# power.net
KiCad netlist of a schematic drawn in Altium Designer
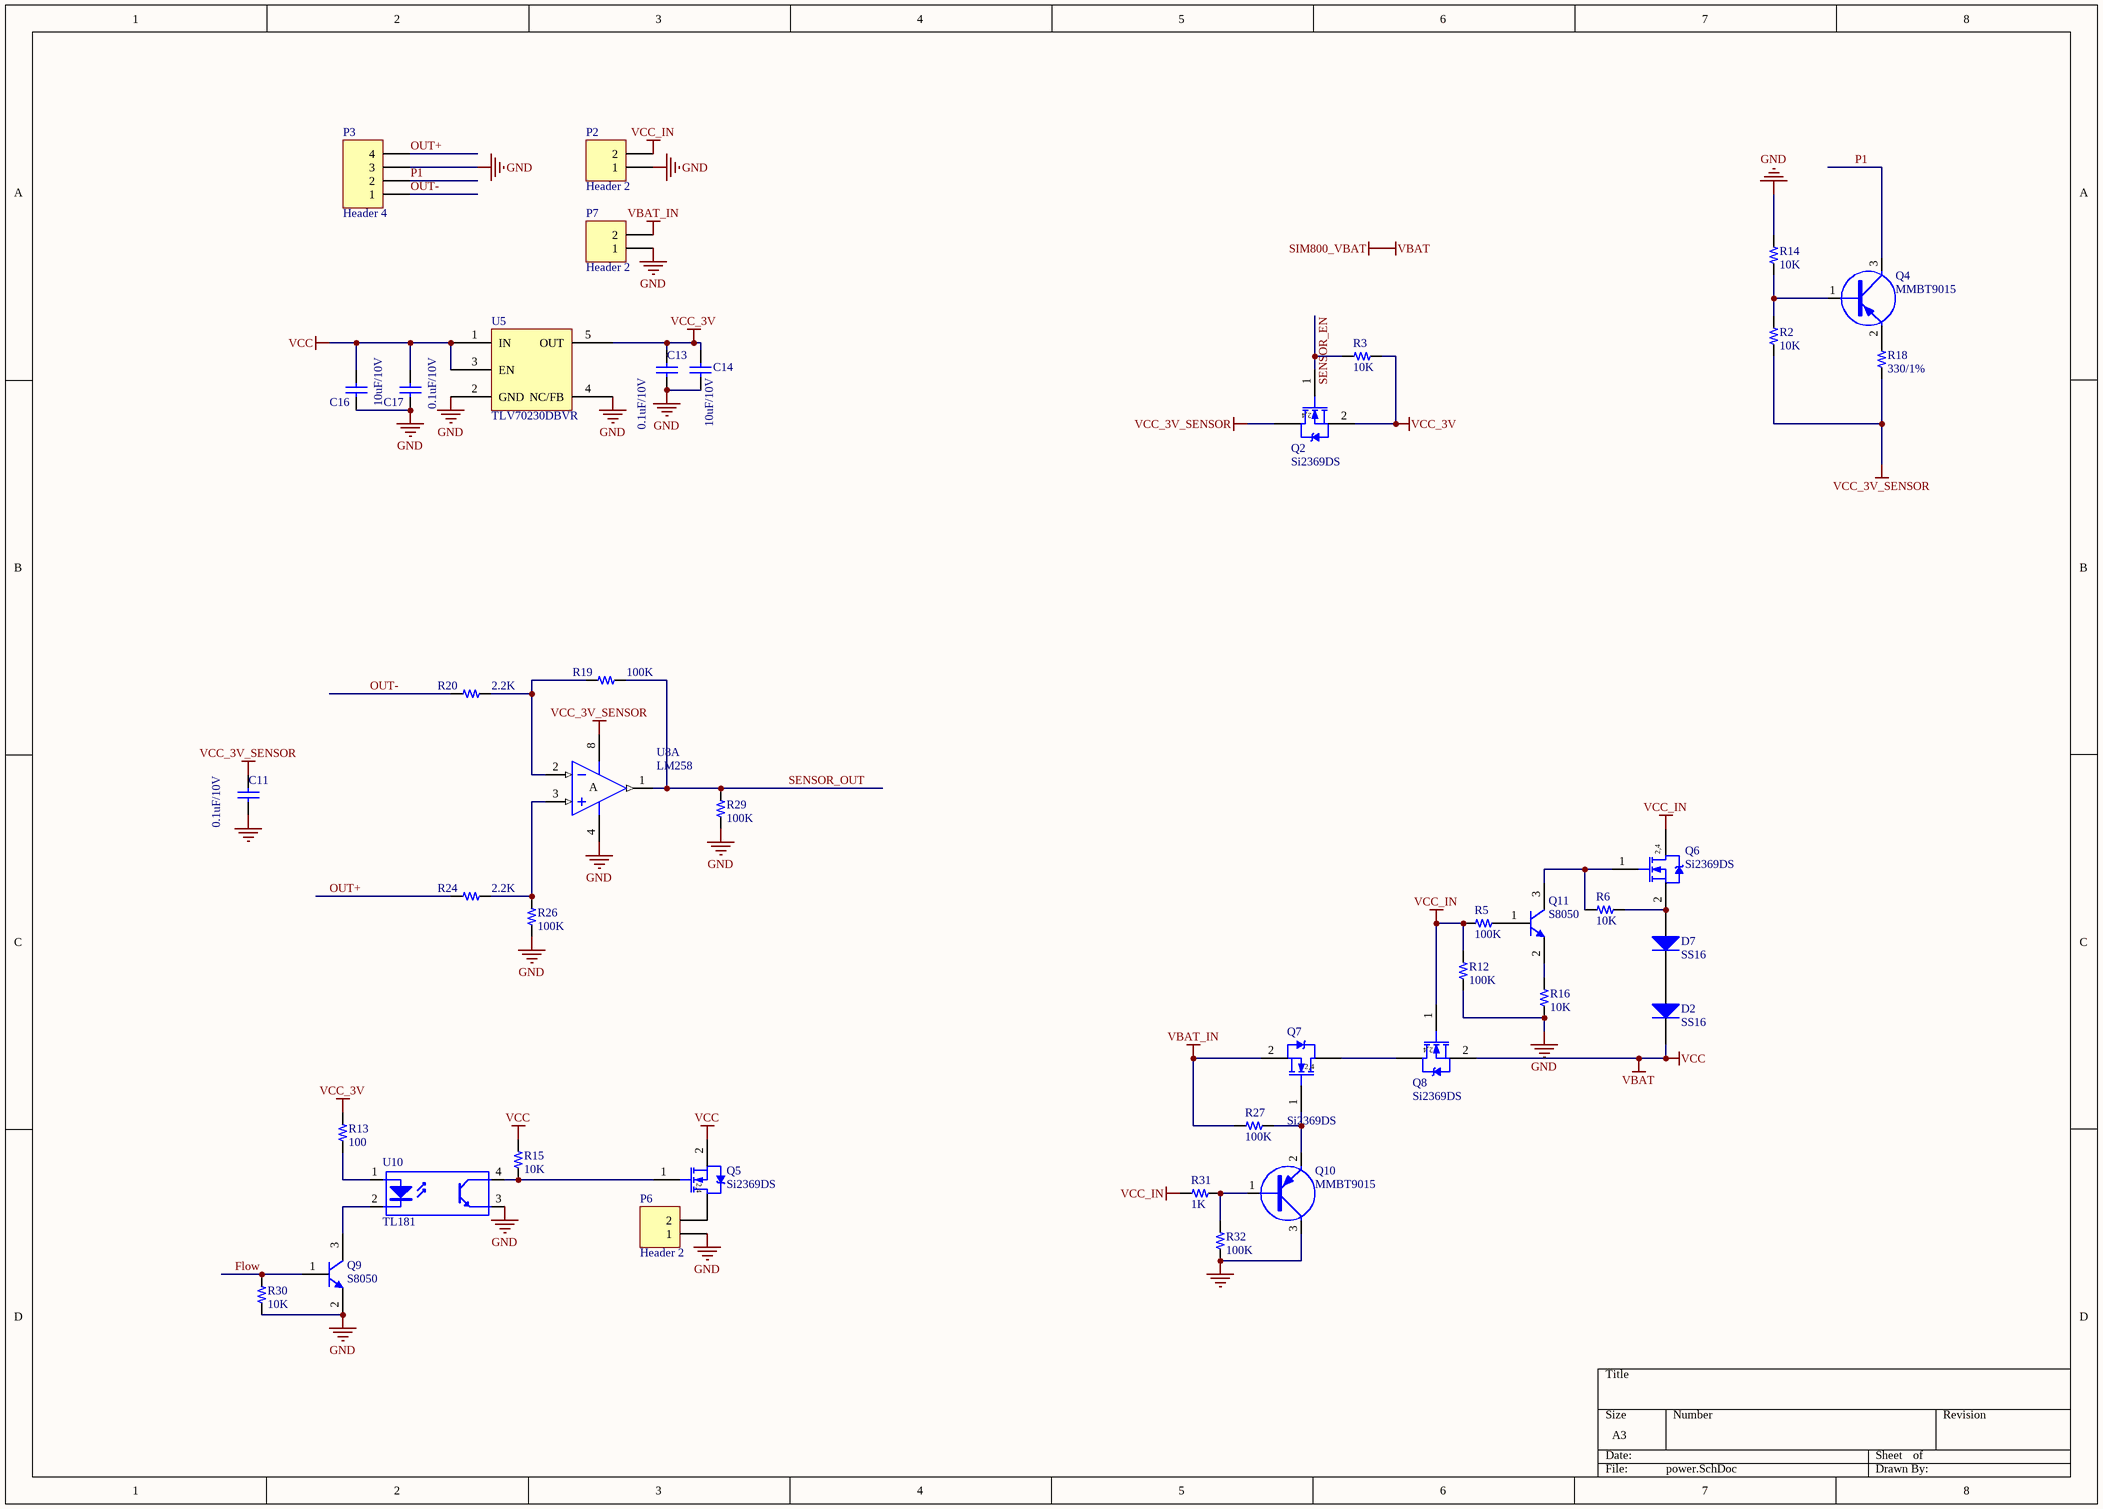
[diagram p0: power.SchDoc]

(export (version "E")
  (design (tool "Eeschema 10.0.6"))
  (components
    (comp (ref "C11")
      (value "0.1uF/10V")
      (footprint "0603C")
      (description "Capacitor")
      (fields (field (name "PUBLISHER") "Altium Limited"))
      (libsource (lib "Miscellaneous Devices") (part "Cap"))
    )
    (comp (ref "C13")
      (value "0.1uF/10V")
      (footprint "0603C")
      (description "Capacitor")
      (fields (field (name "PUBLISHER") "Altium Limited"))
      (libsource (lib "Miscellaneous Devices") (part "Cap"))
    )
    (comp (ref "C14")
      (value "10uF/10V")
      (footprint "0603C")
      (description "Capacitor")
      (fields (field (name "PUBLISHER") "Altium Limited"))
      (libsource (lib "Miscellaneous Devices") (part "Cap"))
    )
    (comp (ref "C16")
      (value "10uF/10V")
      (footprint "0603C")
      (description "Capacitor")
      (fields (field (name "PUBLISHER") "Altium Limited"))
      (libsource (lib "Miscellaneous Devices") (part "Cap"))
    )
    (comp (ref "C17")
      (value "0.1uF/10V")
      (footprint "0603C")
      (description "Capacitor")
      (fields (field (name "PUBLISHER") "Altium Limited"))
      (libsource (lib "Miscellaneous Devices") (part "Cap"))
    )
    (comp (ref "D2")
      (value "SS16")
      (footprint "SMA")
      (description "High Conductance Fast Diode")
      (fields (field (name "PUBLISHER") "Altium Limited"))
      (libsource (lib "Miscellaneous Devices") (part "Diode 1N4148"))
    )
    (comp (ref "D7")
      (value "SS16")
      (footprint "SMA")
      (description "High Conductance Fast Diode")
      (fields (field (name "PUBLISHER") "Altium Limited"))
      (libsource (lib "Miscellaneous Devices") (part "Diode 1N4148"))
    )
    (comp (ref "P2")
      (value "Header 2")
      (footprint "2X2.54MM")
      (description "Header, 2-Pin")
      (fields (field (name "PUBLISHER") "Altium Limited"))
      (libsource (lib "Miscellaneous Connectors") (part "Header 2"))
    )
    (comp (ref "P3")
      (value "Header 4")
      (footprint "HDR1X4")
      (description "Header, 4-Pin")
      (fields (field (name "PUBLISHER") "Altium Limited"))
      (libsource (lib "Miscellaneous Connectors") (part "Header 4"))
    )
    (comp (ref "P6")
      (value "Header 2")
      (footprint "HDR1X2")
      (description "Header, 2-Pin")
      (fields (field (name "PUBLISHER") "Altium Limited"))
      (libsource (lib "Miscellaneous Connectors") (part "Header 2"))
    )
    (comp (ref "P7")
      (value "Header 2")
      (footprint "2X2.54MM")
      (description "Header, 2-Pin")
      (fields (field (name "PUBLISHER") "Altium Limited"))
      (libsource (lib "Miscellaneous Connectors") (part "Header 2"))
    )
    (comp (ref "Q2")
      (value "Si2369DS")
      (footprint "SOT23-3")
      (description "BUK92150-55A")
      (fields (field (name "PUBLISHER") "Altium Limited"))
      (libsource (lib "Schlib1") (part "BUK92150-55A"))
    )
    (comp (ref "Q4") (value "MMBT9015") (footprint "SOT23-3") (libsource (lib "Schlib1") (part "PNP")))
    (comp (ref "Q5")
      (value "Si2369DS")
      (footprint "SOT23-3")
      (description "BUK92150-55A")
      (fields (field (name "PUBLISHER") "Altium Limited"))
      (libsource (lib "") (part "BUK92150-55A_1"))
    )
    (comp (ref "Q6")
      (value "Si2369DS")
      (footprint "SOT23-3")
      (description "BUK92150-55A")
      (fields (field (name "PUBLISHER") "Altium Limited"))
      (libsource (lib "") (part "BUK92150-55A_1"))
    )
    (comp (ref "Q7")
      (value "Si2369DS")
      (footprint "SOT23-3")
      (description "BUK92150-55A")
      (fields (field (name "PUBLISHER") "Altium Limited"))
      (libsource (lib "Schlib1") (part "BUK92150-55A"))
    )
    (comp (ref "Q8")
      (value "Si2369DS")
      (footprint "SOT23-3")
      (description "BUK92150-55A")
      (fields (field (name "PUBLISHER") "Altium Limited"))
      (libsource (lib "Schlib1") (part "BUK92150-55A"))
    )
    (comp (ref "Q9") (value "S8050") (footprint "SOT23-3") (libsource (lib "Schlib1") (part "NPN")))
    (comp (ref "Q10") (value "MMBT9015") (footprint "SOT23-3") (libsource (lib "Schlib1") (part "PNP")))
    (comp (ref "Q11") (value "S8050") (footprint "SOT23-3") (libsource (lib "Schlib1") (part "NPN")))
    (comp (ref "R2") (value "10K") (footprint "0603R") (description "R") (libsource (lib "JRJ_1") (part "R")))
    (comp (ref "R3") (value "10K") (footprint "0603R") (description "R") (libsource (lib "JRJ_1") (part "R")))
    (comp (ref "R5")
      (value "100K")
      (footprint "0603R")
      (description "R")
      (libsource (lib "JRJ_1") (part "R"))
    )
    (comp (ref "R6") (value "10K") (footprint "0603R") (description "R") (libsource (lib "JRJ_1") (part "R")))
    (comp (ref "R12")
      (value "100K")
      (footprint "0603R")
      (description "R")
      (libsource (lib "JRJ_1") (part "R"))
    )
    (comp (ref "R13")
      (value "100")
      (footprint "0603R")
      (description "R")
      (libsource (lib "JRJ_1") (part "R"))
    )
    (comp (ref "R14")
      (value "10K")
      (footprint "0603R")
      (description "R")
      (libsource (lib "JRJ_1") (part "R"))
    )
    (comp (ref "R15")
      (value "10K")
      (footprint "0603R")
      (description "R")
      (libsource (lib "JRJ_1") (part "R"))
    )
    (comp (ref "R16")
      (value "10K")
      (footprint "0603R")
      (description "R")
      (libsource (lib "JRJ_1") (part "R"))
    )
    (comp (ref "R18")
      (value "330/1%")
      (footprint "0603R")
      (description "R")
      (libsource (lib "JRJ_1") (part "R"))
    )
    (comp (ref "R19")
      (value "100K")
      (footprint "0603R")
      (description "R")
      (libsource (lib "JRJ_1") (part "R"))
    )
    (comp (ref "R20")
      (value "2.2K")
      (footprint "0603R")
      (description "R")
      (libsource (lib "JRJ_1") (part "R"))
    )
    (comp (ref "R24")
      (value "2.2K")
      (footprint "0603R")
      (description "R")
      (libsource (lib "JRJ_1") (part "R"))
    )
    (comp (ref "R26")
      (value "100K")
      (footprint "0603R")
      (description "R")
      (libsource (lib "JRJ_1") (part "R"))
    )
    (comp (ref "R27")
      (value "100K")
      (footprint "0603R")
      (description "R")
      (libsource (lib "JRJ_1") (part "R"))
    )
    (comp (ref "R29")
      (value "100K")
      (footprint "0603R")
      (description "R")
      (libsource (lib "JRJ_1") (part "R"))
    )
    (comp (ref "R30")
      (value "10K")
      (footprint "0603R")
      (description "R")
      (libsource (lib "JRJ_1") (part "R"))
    )
    (comp (ref "R31") (value "1K") (footprint "0603R") (description "R") (libsource (lib "JRJ_1") (part "R")))
    (comp (ref "R32")
      (value "100K")
      (footprint "0603R")
      (description "R")
      (libsource (lib "JRJ_1") (part "R"))
    )
    (comp (ref "U5")
      (value "TLV70230DBVR")
      (footprint "SOT23-5(DBV)")
      (libsource (lib "Schlib_20110825") (part "TLV70230DBVR"))
    )
    (comp (ref "U8") (value "LM258") (footprint "so-8") (libsource (lib "Schlib_20110825") (part "LM258")))
    (comp (ref "U10")
      (value "TL181")
      (footprint "DIP-4")
      (description "4-Pin Phototransistor Optocoupler")
      (fields (field (name "PUBLISHER") "Altium Limited"))
      (libsource (lib "Miscellaneous Devices") (part "Optoisolator1"))
    )
  )
  (nets
    (net (code "1") (name "/Flow") (class "Default")
      (node (ref "Q9") (pin "1") (pinfunction "B_1") (pintype "passive"))
      (node (ref "R30") (pin "2") (pintype "passive"))
    )
    (net (code "2") (name "/OUT+") (class "Default")
      (node (ref "P3") (pin "4") (pinfunction "4_4") (pintype "passive"))
      (node (ref "R24") (pin "1") (pintype "passive"))
    )
    (net (code "3") (name "/OUT-") (class "Default")
      (node (ref "P3") (pin "1") (pinfunction "1_1") (pintype "passive"))
      (node (ref "R20") (pin "1") (pintype "passive"))
    )
    (net (code "4") (name "/P1") (class "Default")
      (node (ref "P3") (pin "2") (pinfunction "2_2") (pintype "passive"))
      (node (ref "Q4") (pin "3") (pinfunction "C_3") (pintype "passive"))
    )
    (net (code "5") (name "/SENSOR_EN") (class "Default")
      (node (ref "Q2") (pin "1") (pinfunction "G_1") (pintype "passive"))
      (node (ref "R3") (pin "2") (pintype "passive"))
    )
    (net (code "6") (name "/SENSOR_OUT") (class "Default")
      (node (ref "R19") (pin "2") (pintype "passive"))
      (node (ref "R29") (pin "2") (pintype "passive"))
      (node (ref "U8") (pin "1") (pinfunction "OUT_1") (pintype "output"))
    )
    (net (code "7") (name "GND") (class "Default")
      (node (ref "C11") (pin "2") (pinfunction "2_2") (pintype "passive"))
      (node (ref "C13") (pin "2") (pinfunction "2_2") (pintype "passive"))
      (node (ref "C14") (pin "1") (pinfunction "1_1") (pintype "passive"))
      (node (ref "C16") (pin "1") (pinfunction "1_1") (pintype "passive"))
      (node (ref "C17") (pin "2") (pinfunction "2_2") (pintype "passive"))
      (node (ref "P2") (pin "1") (pinfunction "1_1") (pintype "passive"))
      (node (ref "P3") (pin "3") (pinfunction "3_3") (pintype "passive"))
      (node (ref "P6") (pin "1") (pinfunction "1_1") (pintype "passive"))
      (node (ref "P7") (pin "1") (pinfunction "1_1") (pintype "passive"))
      (node (ref "Q10") (pin "3") (pinfunction "C_3") (pintype "passive"))
      (node (ref "Q9") (pin "2") (pinfunction "E_2") (pintype "passive"))
      (node (ref "R12") (pin "2") (pintype "passive"))
      (node (ref "R14") (pin "2") (pintype "passive"))
      (node (ref "R16") (pin "1") (pintype "passive"))
      (node (ref "R26") (pin "1") (pintype "passive"))
      (node (ref "R29") (pin "1") (pintype "passive"))
      (node (ref "R30") (pin "1") (pintype "passive"))
      (node (ref "R32") (pin "1") (pintype "passive"))
      (node (ref "U10") (pin "3") (pinfunction "E_3") (pintype "passive"))
      (node (ref "U5") (pin "2") (pinfunction "GND_2") (pintype "passive"))
      (node (ref "U5") (pin "4") (pinfunction "NC/FB_4") (pintype "passive"))
      (node (ref "U8") (pin "4") (pinfunction "V-_4") (pintype "power_in"))
    )
    (net (code "8") (name "Net-(D2-A)") (class "Default")
      (node (ref "D2") (pin "1") (pinfunction "A_1") (pintype "passive"))
      (node (ref "D7") (pin "2") (pinfunction "K_2") (pintype "passive"))
    )
    (net (code "9") (name "Net-(D7-A)") (class "Default")
      (node (ref "D7") (pin "1") (pinfunction "A_1") (pintype "passive"))
      (node (ref "Q6") (pin "2") (pinfunction "S_2") (pintype "passive"))
      (node (ref "R6") (pin "1") (pintype "passive"))
    )
    (net (code "10") (name "Net-(Q4-B)") (class "Default")
      (node (ref "Q4") (pin "1") (pinfunction "B_1") (pintype "passive"))
      (node (ref "R14") (pin "1") (pintype "passive"))
      (node (ref "R2") (pin "2") (pintype "passive"))
    )
    (net (code "11") (name "Net-(Q4-E)") (class "Default")
      (node (ref "Q4") (pin "2") (pinfunction "E_2") (pintype "passive"))
      (node (ref "R18") (pin "2") (pintype "passive"))
    )
    (net (code "12") (name "Net-(Q5-D)") (class "Default")
      (node (ref "P6") (pin "2") (pinfunction "2_2") (pintype "passive"))
      (node (ref "Q5") (pin "3") (pinfunction "D_3") (pintype "passive"))
    )
    (net (code "13") (name "Net-(Q5-G)") (class "Default")
      (node (ref "Q5") (pin "1") (pinfunction "G_1") (pintype "passive"))
      (node (ref "R15") (pin "1") (pintype "passive"))
      (node (ref "U10") (pin "4") (pinfunction "C_4") (pintype "passive"))
    )
    (net (code "14") (name "Net-(Q7-D)") (class "Default")
      (node (ref "Q7") (pin "3") (pinfunction "D_3") (pintype "passive"))
      (node (ref "Q8") (pin "3") (pinfunction "D_3") (pintype "passive"))
    )
    (net (code "15") (name "Net-(Q9-C)") (class "Default")
      (node (ref "Q9") (pin "3") (pinfunction "C_3") (pintype "passive"))
      (node (ref "U10") (pin "2") (pinfunction "K_2") (pintype "passive"))
    )
    (net (code "16") (name "Net-(Q10-B)") (class "Default")
      (node (ref "Q10") (pin "1") (pinfunction "B_1") (pintype "passive"))
      (node (ref "R31") (pin "2") (pintype "passive"))
      (node (ref "R32") (pin "2") (pintype "passive"))
    )
    (net (code "17") (name "Net-(Q10-E)") (class "Default")
      (node (ref "Q10") (pin "2") (pinfunction "E_2") (pintype "passive"))
      (node (ref "Q7") (pin "1") (pinfunction "G_1") (pintype "passive"))
      (node (ref "R27") (pin "2") (pintype "passive"))
    )
    (net (code "18") (name "Net-(Q11-B)") (class "Default")
      (node (ref "Q11") (pin "1") (pinfunction "B_1") (pintype "passive"))
      (node (ref "R5") (pin "2") (pintype "passive"))
    )
    (net (code "19") (name "Net-(Q11-C)") (class "Default")
      (node (ref "Q11") (pin "3") (pinfunction "C_3") (pintype "passive"))
      (node (ref "Q6") (pin "1") (pinfunction "G_1") (pintype "passive"))
      (node (ref "R6") (pin "2") (pintype "passive"))
    )
    (net (code "20") (name "Net-(Q11-E)") (class "Default")
      (node (ref "Q11") (pin "2") (pinfunction "E_2") (pintype "passive"))
      (node (ref "R16") (pin "2") (pintype "passive"))
    )
    (net (code "21") (name "Net-(U8A-IN+)") (class "Default")
      (node (ref "R24") (pin "2") (pintype "passive"))
      (node (ref "R26") (pin "2") (pintype "passive"))
      (node (ref "U8") (pin "3") (pinfunction "IN+_3") (pintype "input"))
    )
    (net (code "22") (name "Net-(U8A-IN-)") (class "Default")
      (node (ref "R19") (pin "1") (pintype "passive"))
      (node (ref "R20") (pin "2") (pintype "passive"))
      (node (ref "U8") (pin "2") (pinfunction "IN-_2") (pintype "input"))
    )
    (net (code "23") (name "Net-(U10-A)") (class "Default")
      (node (ref "R13") (pin "1") (pintype "passive"))
      (node (ref "U10") (pin "1") (pinfunction "A_1") (pintype "passive"))
    )
    (net (code "24") (name "SIM800_VBAT") (class "Default")
      (node (ref "C16") (pin "2") (pinfunction "2_2") (pintype "passive"))
      (node (ref "C17") (pin "1") (pinfunction "1_1") (pintype "passive"))
      (node (ref "D2") (pin "2") (pinfunction "K_2") (pintype "passive"))
      (node (ref "Q5") (pin "2") (pinfunction "S_2") (pintype "passive"))
      (node (ref "Q8") (pin "2") (pinfunction "S_2") (pintype "passive"))
      (node (ref "R15") (pin "2") (pintype "passive"))
      (node (ref "U5") (pin "1") (pinfunction "IN_1") (pintype "passive"))
      (node (ref "U5") (pin "3") (pinfunction "EN_3") (pintype "passive"))
    )
    (net (code "25") (name "VBAT_IN") (class "Default")
      (node (ref "P7") (pin "2") (pinfunction "2_2") (pintype "passive"))
      (node (ref "Q7") (pin "2") (pinfunction "S_2") (pintype "passive"))
      (node (ref "R27") (pin "1") (pintype "passive"))
    )
    (net (code "26") (name "VCC_3V") (class "Default")
      (node (ref "C13") (pin "1") (pinfunction "1_1") (pintype "passive"))
      (node (ref "C14") (pin "2") (pinfunction "2_2") (pintype "passive"))
      (node (ref "Q2") (pin "2") (pinfunction "S_2") (pintype "passive"))
      (node (ref "R13") (pin "2") (pintype "passive"))
      (node (ref "R3") (pin "1") (pintype "passive"))
      (node (ref "U5") (pin "5") (pinfunction "OUT_5") (pintype "passive"))
    )
    (net (code "27") (name "VCC_3V_SENSOR") (class "Default")
      (node (ref "C11") (pin "1") (pinfunction "1_1") (pintype "passive"))
      (node (ref "Q2") (pin "3") (pinfunction "D_3") (pintype "passive"))
      (node (ref "R18") (pin "1") (pintype "passive"))
      (node (ref "R2") (pin "1") (pintype "passive"))
      (node (ref "U8") (pin "8") (pinfunction "V+_8") (pintype "power_in"))
    )
    (net (code "28") (name "VCC_IN") (class "Default")
      (node (ref "P2") (pin "2") (pinfunction "2_2") (pintype "passive"))
      (node (ref "Q6") (pin "3") (pinfunction "D_3") (pintype "passive"))
      (node (ref "Q8") (pin "1") (pinfunction "G_1") (pintype "passive"))
      (node (ref "R12") (pin "1") (pintype "passive"))
      (node (ref "R31") (pin "1") (pintype "passive"))
      (node (ref "R5") (pin "1") (pintype "passive"))
    )
  )
)
